# Stepper_Controller.net
KiCad netlist of a schematic drawn in EAGLE
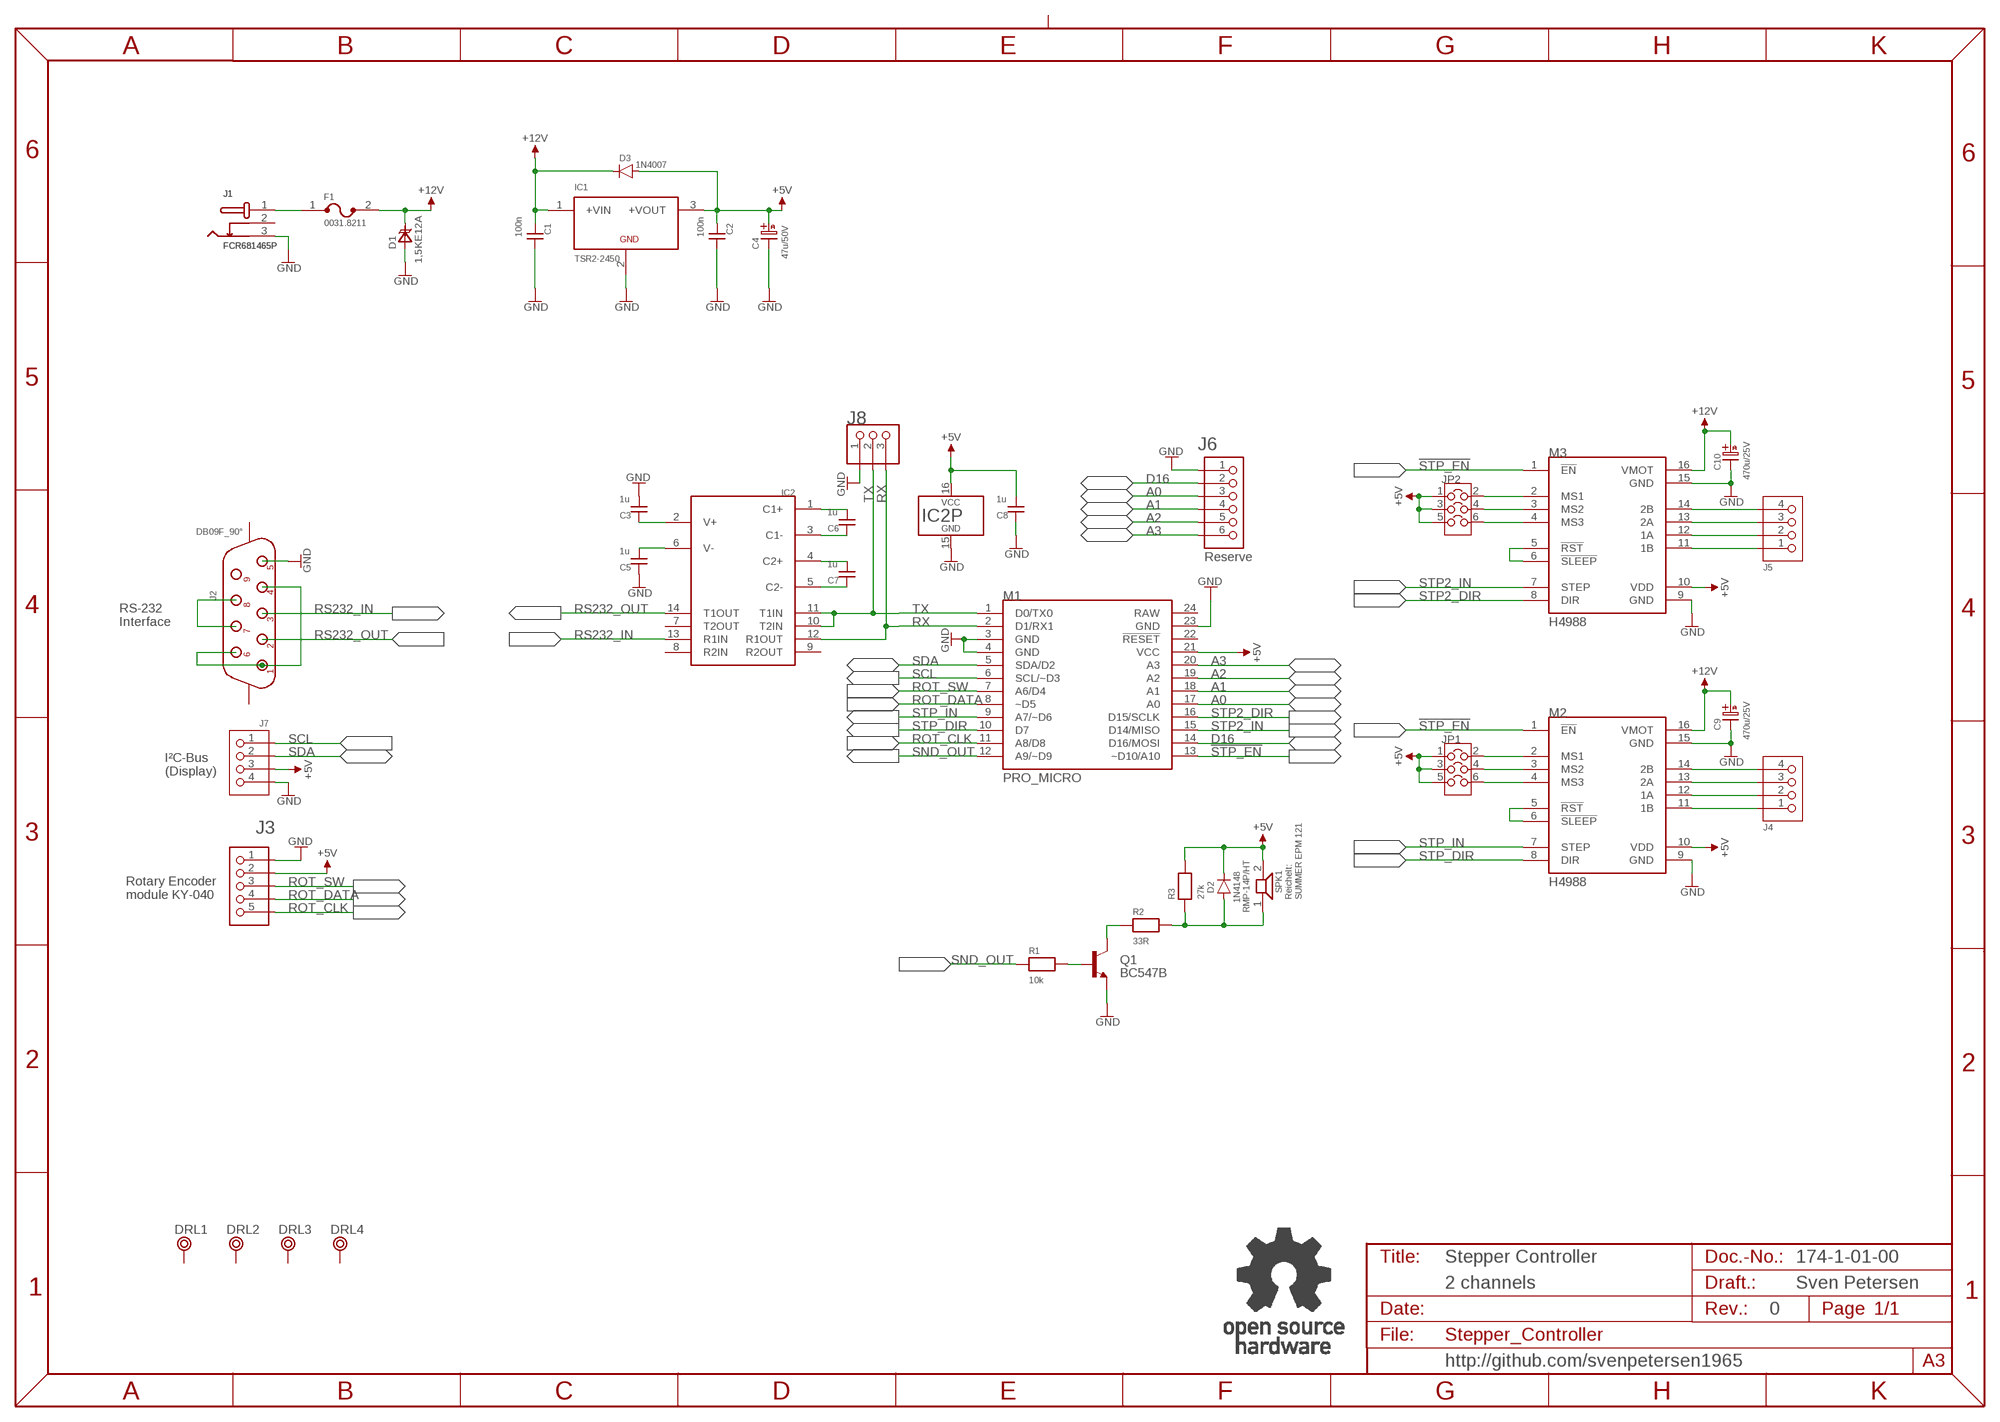
[diagram p0: schematic, sheet 1]

(export (version "E")
  (design (tool "Eeschema 10.0.6"))
  (components
    (comp (ref "C1")
      (value "100n")
      (footprint "eagle-import:C-2,5")
      (libsource (lib "eagle-import") (part "CAP01"))
    )
    (comp (ref "C2")
      (value "100n")
      (footprint "eagle-import:C-2,5")
      (libsource (lib "eagle-import") (part "CAP01"))
    )
    (comp (ref "C3")
      (value "1u")
      (footprint "eagle-import:C-5")
      (libsource (lib "eagle-import") (part "CAP02"))
    )
    (comp (ref "C4")
      (value "47u/50V")
      (footprint "eagle-import:C07_2,5")
      (libsource (lib "eagle-import") (part "C07/2,5"))
    )
    (comp (ref "C5")
      (value "1u")
      (footprint "eagle-import:C-5")
      (libsource (lib "eagle-import") (part "CAP02"))
    )
    (comp (ref "C6")
      (value "1u")
      (footprint "eagle-import:C-5")
      (libsource (lib "eagle-import") (part "CAP02"))
    )
    (comp (ref "C7")
      (value "1u")
      (footprint "eagle-import:C-5")
      (libsource (lib "eagle-import") (part "CAP02"))
    )
    (comp (ref "C8")
      (value "1u")
      (footprint "eagle-import:C-5")
      (libsource (lib "eagle-import") (part "CAP02"))
    )
    (comp (ref "C9")
      (value "470u/25V")
      (footprint "eagle-import:C08_3,5")
      (libsource (lib "eagle-import") (part "C08/3,5"))
    )
    (comp (ref "C10")
      (value "470u/25V")
      (footprint "eagle-import:C08_3,5")
      (libsource (lib "eagle-import") (part "C08/3,5"))
    )
    (comp (ref "D1")
      (value "1,5KE12A")
      (footprint "eagle-import:DO-201")
      (libsource (lib "eagle-import") (part "1,5KE12A"))
    )
    (comp (ref "D2")
      (value "1N4148")
      (footprint "eagle-import:DO-35")
      (libsource (lib "eagle-import") (part "1N4148"))
    )
    (comp (ref "D3")
      (value "1N4007")
      (footprint "eagle-import:DO-41")
      (libsource (lib "eagle-import") (part "1N4007"))
    )
    (comp (ref "DRL1")
      (value "BOHR3,5")
      (footprint "eagle-import:BOHR3,5")
      (libsource (lib "eagle-import") (part "BOHR3,5"))
    )
    (comp (ref "DRL2")
      (value "BOHR3,5")
      (footprint "eagle-import:BOHR3,5")
      (libsource (lib "eagle-import") (part "BOHR3,5"))
    )
    (comp (ref "DRL3")
      (value "BOHR3,5")
      (footprint "eagle-import:BOHR3,5")
      (libsource (lib "eagle-import") (part "BOHR3,5"))
    )
    (comp (ref "DRL4")
      (value "BOHR3,5")
      (footprint "eagle-import:BOHR3,5")
      (libsource (lib "eagle-import") (part "BOHR3,5"))
    )
    (comp (ref "F1")
      (value "0031.8211")
      (footprint "eagle-import:0031.8211")
      (libsource (lib "eagle-import") (part "0031.8211"))
    )
    (comp (ref "IC1")
      (value "TSR2-2450")
      (footprint "eagle-import:TSR2")
      (libsource (lib "eagle-import") (part "TSR2"))
    )
    (comp (ref "IC2")
      (value "MAX-232")
      (footprint "eagle-import:DIL-16")
      (libsource (lib "eagle-import") (part "MAX-232"))
    )
    (comp (ref "J1")
      (value "FCR681465P")
      (footprint "eagle-import:FCR681465P")
      (libsource (lib "eagle-import") (part "FCR681465P"))
    )
    (comp (ref "J2")
      (value "DB09F_90°")
      (footprint "eagle-import:DS09F-H")
      (libsource (lib "eagle-import") (part "DS09F-H-CL"))
    )
    (comp (ref "J3")
      (value "6410-5P")
      (footprint "eagle-import:6410-5P")
      (libsource (lib "eagle-import") (part "6410-5P"))
    )
    (comp (ref "J4")
      (value "6410-4P")
      (footprint "eagle-import:6410-4P")
      (libsource (lib "eagle-import") (part "6410-4P"))
    )
    (comp (ref "J5")
      (value "6410-4P")
      (footprint "eagle-import:6410-4P")
      (libsource (lib "eagle-import") (part "6410-4P"))
    )
    (comp (ref "J6")
      (value "PINHD-1X6")
      (footprint "eagle-import:1X06")
      (libsource (lib "eagle-import") (part "PINHD-1X6"))
    )
    (comp (ref "J7")
      (value "6410-4P")
      (footprint "eagle-import:6410-4P")
      (libsource (lib "eagle-import") (part "6410-4P"))
    )
    (comp (ref "J8")
      (value "PINHD-1X3")
      (footprint "eagle-import:1X03")
      (libsource (lib "eagle-import") (part "PINHD-1X3"))
    )
    (comp (ref "JP1")
      (value "COMBI-3X2P")
      (footprint "eagle-import:COMBI-3X2")
      (libsource (lib "eagle-import") (part "COMBI-3X2P"))
    )
    (comp (ref "JP2")
      (value "COMBI-3X2P")
      (footprint "eagle-import:COMBI-3X2")
      (libsource (lib "eagle-import") (part "COMBI-3X2P"))
    )
    (comp (ref "M1")
      (value "PRO_MICRO")
      (footprint "eagle-import:PRO_MICRO")
      (libsource (lib "eagle-import") (part "PRO_MICRO"))
    )
    (comp (ref "M2")
      (value "H4988")
      (footprint "eagle-import:H4988")
      (libsource (lib "eagle-import") (part "H4988"))
    )
    (comp (ref "M3")
      (value "H4988")
      (footprint "eagle-import:H4988")
      (libsource (lib "eagle-import") (part "H4988"))
    )
    (comp (ref "Q1")
      (value "BC547B")
      (footprint "eagle-import:TO92")
      (libsource (lib "eagle-import") (part "BC547B"))
    )
    (comp (ref "R1")
      (value "10k")
      (footprint "eagle-import:R-10")
      (libsource (lib "eagle-import") (part "RES04"))
    )
    (comp (ref "R2")
      (value "33R")
      (footprint "eagle-import:R-10")
      (libsource (lib "eagle-import") (part "RES04"))
    )
    (comp (ref "R3")
      (value "27k")
      (footprint "eagle-import:R-10")
      (libsource (lib "eagle-import") (part "RES04"))
    )
    (comp (ref "SPK1")
      (value "RMP-14P/HT")
      (footprint "eagle-import:RMP-14P_HT")
      (libsource (lib "eagle-import") (part "RMP-14P/HT"))
    )
    (comp (ref "U$2")
      (value "OPEN_SOURCE_HW")
      (footprint "eagle-import:OPENHW")
      (libsource (lib "eagle-import") (part "OPEN_SOURCE_HW"))
    )
  )
  (nets
    (net (code "1") (name "+5V") (class "Default")
      (node (ref "C2") (pin "1") (pinfunction "1_1") (pintype "passive"))
      (node (ref "C4") (pin "A") (pinfunction "+_A") (pintype "passive"))
      (node (ref "C8") (pin "2") (pinfunction "2_2") (pintype "passive"))
      (node (ref "D2") (pin "K") (pinfunction "K_K") (pintype "passive"))
      (node (ref "D3") (pin "A") (pinfunction "A_A") (pintype "passive"))
      (node (ref "IC1") (pin "3") (pinfunction "+VOUT_3") (pintype "output"))
      (node (ref "IC2") (pin "16") (pinfunction "VCC_16") (pintype "power_in"))
      (node (ref "J3") (pin "2") (pinfunction "2_2") (pintype "passive"))
      (node (ref "J7") (pin "3") (pinfunction "3_3") (pintype "passive"))
      (node (ref "JP1") (pin "1") (pinfunction "1_1") (pintype "bidirectional"))
      (node (ref "JP1") (pin "3") (pinfunction "3_3") (pintype "bidirectional"))
      (node (ref "JP1") (pin "5") (pinfunction "5_5") (pintype "bidirectional"))
      (node (ref "JP2") (pin "1") (pinfunction "1_1") (pintype "bidirectional"))
      (node (ref "JP2") (pin "3") (pinfunction "3_3") (pintype "bidirectional"))
      (node (ref "JP2") (pin "5") (pinfunction "5_5") (pintype "bidirectional"))
      (node (ref "M1") (pin "21") (pinfunction "VCC_21") (pintype "power_in"))
      (node (ref "M2") (pin "10") (pinfunction "VDD_10") (pintype "power_in"))
      (node (ref "M3") (pin "10") (pinfunction "VDD_10") (pintype "power_in"))
      (node (ref "R3") (pin "2") (pinfunction "2_2") (pintype "passive"))
      (node (ref "SPK1") (pin "2") (pinfunction "2_2") (pintype "bidirectional"))
    )
    (net (code "2") (name "+12V") (class "Default")
      (node (ref "C1") (pin "1") (pinfunction "1_1") (pintype "passive"))
      (node (ref "C10") (pin "+") (pinfunction "+_+") (pintype "passive"))
      (node (ref "C9") (pin "+") (pinfunction "+_+") (pintype "passive"))
      (node (ref "D1") (pin "K") (pinfunction "K_K") (pintype "passive"))
      (node (ref "D3") (pin "K") (pinfunction "K_K") (pintype "passive"))
      (node (ref "F1") (pin "2") (pinfunction "2_2") (pintype "passive"))
      (node (ref "IC1") (pin "1") (pinfunction "+VIN_1") (pintype "input"))
      (node (ref "M2") (pin "16") (pinfunction "VMOT_16") (pintype "power_in"))
      (node (ref "M3") (pin "16") (pinfunction "VMOT_16") (pintype "power_in"))
    )
    (net (code "3") (name "/A0") (class "Default")
      (node (ref "J6") (pin "3") (pinfunction "3_3") (pintype "passive"))
      (node (ref "M1") (pin "17") (pinfunction "A0_17") (pintype "bidirectional"))
    )
    (net (code "4") (name "/A1") (class "Default")
      (node (ref "J6") (pin "4") (pinfunction "4_4") (pintype "passive"))
      (node (ref "M1") (pin "18") (pinfunction "A1_18") (pintype "bidirectional"))
    )
    (net (code "5") (name "/A2") (class "Default")
      (node (ref "J6") (pin "5") (pinfunction "5_5") (pintype "passive"))
      (node (ref "M1") (pin "19") (pinfunction "A2_19") (pintype "bidirectional"))
    )
    (net (code "6") (name "/A3") (class "Default")
      (node (ref "J6") (pin "6") (pinfunction "6_6") (pintype "passive"))
      (node (ref "M1") (pin "20") (pinfunction "A3_20") (pintype "bidirectional"))
    )
    (net (code "7") (name "/D16") (class "Default")
      (node (ref "J6") (pin "2") (pinfunction "2_2") (pintype "passive"))
      (node (ref "M1") (pin "14") (pinfunction "D16/MOSI_14") (pintype "bidirectional"))
    )
    (net (code "8") (name "/RAW") (class "Default")
      (node (ref "M1") (pin "24") (pinfunction "RAW_24") (pintype "power_in"))
    )
    (net (code "9") (name "/ROT_CLK") (class "Default")
      (node (ref "J3") (pin "5") (pinfunction "5_5") (pintype "passive"))
      (node (ref "M1") (pin "11") (pinfunction "A8/D8_11") (pintype "bidirectional"))
    )
    (net (code "10") (name "/ROT_DATA") (class "Default")
      (node (ref "J3") (pin "4") (pinfunction "4_4") (pintype "passive"))
      (node (ref "M1") (pin "8") (pinfunction "~{D5}_8") (pintype "bidirectional"))
    )
    (net (code "11") (name "/ROT_SW") (class "Default")
      (node (ref "J3") (pin "3") (pinfunction "3_3") (pintype "passive"))
      (node (ref "M1") (pin "7") (pinfunction "A6/D4_7") (pintype "bidirectional"))
    )
    (net (code "12") (name "/RS232_IN") (class "Default")
      (node (ref "IC2") (pin "13") (pinfunction "R1IN_13") (pintype "input"))
      (node (ref "J2") (pin "3") (pinfunction "3_3") (pintype "passive"))
    )
    (net (code "13") (name "/RS232_OUT") (class "Default")
      (node (ref "IC2") (pin "14") (pinfunction "T1OUT_14") (pintype "output"))
      (node (ref "J2") (pin "2") (pinfunction "2_2") (pintype "passive"))
    )
    (net (code "14") (name "/RX") (class "Default")
      (node (ref "IC2") (pin "12") (pinfunction "R1OUT_12") (pintype "output"))
      (node (ref "J8") (pin "3") (pinfunction "3_3") (pintype "passive"))
      (node (ref "M1") (pin "2") (pinfunction "D1/RX1_2") (pintype "bidirectional"))
    )
    (net (code "15") (name "/SCL") (class "Default")
      (node (ref "J7") (pin "1") (pinfunction "1_1") (pintype "passive"))
      (node (ref "M1") (pin "6") (pinfunction "SCL/~{D3}_6") (pintype "bidirectional"))
    )
    (net (code "16") (name "/SDA") (class "Default")
      (node (ref "J7") (pin "2") (pinfunction "2_2") (pintype "passive"))
      (node (ref "M1") (pin "5") (pinfunction "SDA/D2_5") (pintype "bidirectional"))
    )
    (net (code "17") (name "/SND_OUT") (class "Default")
      (node (ref "M1") (pin "12") (pinfunction "A9/~{D9}_12") (pintype "bidirectional"))
      (node (ref "R1") (pin "1") (pinfunction "1_1") (pintype "passive"))
    )
    (net (code "18") (name "/STP2_DIR") (class "Default")
      (node (ref "M1") (pin "16") (pinfunction "D15/SCLK_16") (pintype "bidirectional"))
      (node (ref "M3") (pin "8") (pinfunction "DIR_8") (pintype "input"))
    )
    (net (code "19") (name "/STP2_IN") (class "Default")
      (node (ref "M1") (pin "15") (pinfunction "D14/MISO_15") (pintype "bidirectional"))
      (node (ref "M3") (pin "7") (pinfunction "STEP_7") (pintype "input"))
    )
    (net (code "20") (name "/STP_DIR") (class "Default")
      (node (ref "M1") (pin "10") (pinfunction "D7_10") (pintype "bidirectional"))
      (node (ref "M2") (pin "8") (pinfunction "DIR_8") (pintype "input"))
    )
    (net (code "21") (name "/STP_IN") (class "Default")
      (node (ref "M1") (pin "9") (pinfunction "A7/~{D6}_9") (pintype "bidirectional"))
      (node (ref "M2") (pin "7") (pinfunction "STEP_7") (pintype "input"))
    )
    (net (code "22") (name "/TX") (class "Default")
      (node (ref "IC2") (pin "10") (pinfunction "T2IN_10") (pintype "input"))
      (node (ref "IC2") (pin "11") (pinfunction "T1IN_11") (pintype "input"))
      (node (ref "J8") (pin "2") (pinfunction "2_2") (pintype "passive"))
      (node (ref "M1") (pin "1") (pinfunction "D0/TX0_1") (pintype "bidirectional"))
    )
    (net (code "23") (name "/~{STP_EN}") (class "Default")
      (node (ref "M1") (pin "13") (pinfunction "~{D10/A10}_13") (pintype "bidirectional"))
      (node (ref "M2") (pin "1") (pinfunction "~{EN}_1") (pintype "input"))
      (node (ref "M3") (pin "1") (pinfunction "~{EN}_1") (pintype "input"))
    )
    (net (code "24") (name "GND") (class "Default")
      (node (ref "C1") (pin "2") (pinfunction "2_2") (pintype "passive"))
      (node (ref "C10") (pin "-") (pinfunction "-_-") (pintype "passive"))
      (node (ref "C2") (pin "2") (pinfunction "2_2") (pintype "passive"))
      (node (ref "C3") (pin "2") (pinfunction "2_2") (pintype "passive"))
      (node (ref "C4") (pin "K") (pinfunction "-_K") (pintype "passive"))
      (node (ref "C5") (pin "1") (pinfunction "1_1") (pintype "passive"))
      (node (ref "C8") (pin "1") (pinfunction "1_1") (pintype "passive"))
      (node (ref "C9") (pin "-") (pinfunction "-_-") (pintype "passive"))
      (node (ref "D1") (pin "A") (pinfunction "A_A") (pintype "passive"))
      (node (ref "IC1") (pin "2") (pinfunction "GND_2") (pintype "passive"))
      (node (ref "IC2") (pin "15") (pinfunction "GND_15") (pintype "power_in"))
      (node (ref "J1") (pin "3") (pinfunction "3_3") (pintype "bidirectional"))
      (node (ref "J2") (pin "5") (pinfunction "5_5") (pintype "passive"))
      (node (ref "J3") (pin "1") (pinfunction "1_1") (pintype "passive"))
      (node (ref "J6") (pin "1") (pinfunction "1_1") (pintype "passive"))
      (node (ref "J7") (pin "4") (pinfunction "4_4") (pintype "passive"))
      (node (ref "J8") (pin "1") (pinfunction "1_1") (pintype "passive"))
      (node (ref "M1") (pin "23") (pinfunction "GND_23") (pintype "power_in"))
      (node (ref "M1") (pin "3") (pinfunction "GND_3") (pintype "power_in"))
      (node (ref "M1") (pin "4") (pinfunction "GND_4") (pintype "power_in"))
      (node (ref "M2") (pin "15") (pinfunction "GND_15") (pintype "power_in"))
      (node (ref "M2") (pin "9") (pinfunction "GND_9") (pintype "power_in"))
      (node (ref "M3") (pin "15") (pinfunction "GND_15") (pintype "power_in"))
      (node (ref "M3") (pin "9") (pinfunction "GND_9") (pintype "power_in"))
      (node (ref "Q1") (pin "1") (pinfunction "E_1") (pintype "passive"))
    )
    (net (code "25") (name "Net-(D2-PadA)") (class "Default")
      (node (ref "D2") (pin "A") (pinfunction "A_A") (pintype "passive"))
      (node (ref "R2") (pin "2") (pinfunction "2_2") (pintype "passive"))
      (node (ref "R3") (pin "1") (pinfunction "1_1") (pintype "passive"))
      (node (ref "SPK1") (pin "1") (pinfunction "1_1") (pintype "bidirectional"))
    )
    (net (code "26") (name "Net-(F1-Pad1)") (class "Default")
      (node (ref "F1") (pin "1") (pinfunction "1_1") (pintype "passive"))
      (node (ref "J1") (pin "1") (pinfunction "1_1") (pintype "bidirectional"))
    )
    (net (code "27") (name "Net-(IC2A-C1+)") (class "Default")
      (node (ref "C6") (pin "2") (pinfunction "2_2") (pintype "passive"))
      (node (ref "IC2") (pin "1") (pinfunction "C1+_1") (pintype "bidirectional"))
    )
    (net (code "28") (name "Net-(IC2A-C1-)") (class "Default")
      (node (ref "C6") (pin "1") (pinfunction "1_1") (pintype "passive"))
      (node (ref "IC2") (pin "3") (pinfunction "C1-_3") (pintype "bidirectional"))
    )
    (net (code "29") (name "Net-(IC2A-C2+)") (class "Default")
      (node (ref "C7") (pin "2") (pinfunction "2_2") (pintype "passive"))
      (node (ref "IC2") (pin "4") (pinfunction "C2+_4") (pintype "bidirectional"))
    )
    (net (code "30") (name "Net-(IC2A-C2-)") (class "Default")
      (node (ref "C7") (pin "1") (pinfunction "1_1") (pintype "passive"))
      (node (ref "IC2") (pin "5") (pinfunction "C2-_5") (pintype "bidirectional"))
    )
    (net (code "31") (name "Net-(IC2A-V+)") (class "Default")
      (node (ref "C3") (pin "1") (pinfunction "1_1") (pintype "passive"))
      (node (ref "IC2") (pin "2") (pinfunction "V+_2") (pintype "bidirectional"))
    )
    (net (code "32") (name "Net-(IC2A-V-)") (class "Default")
      (node (ref "C5") (pin "2") (pinfunction "2_2") (pintype "passive"))
      (node (ref "IC2") (pin "6") (pinfunction "V-_6") (pintype "bidirectional"))
    )
    (net (code "33") (name "Net-(J2-Pad1)") (class "Default")
      (node (ref "J2") (pin "1") (pinfunction "1_1") (pintype "passive"))
      (node (ref "J2") (pin "4") (pinfunction "4_4") (pintype "passive"))
      (node (ref "J2") (pin "6") (pinfunction "6_6") (pintype "passive"))
    )
    (net (code "34") (name "Net-(J2-Pad7)") (class "Default")
      (node (ref "J2") (pin "7") (pinfunction "7_7") (pintype "passive"))
      (node (ref "J2") (pin "8") (pinfunction "8_8") (pintype "passive"))
    )
    (net (code "35") (name "Net-(M2-1A)") (class "Default")
      (node (ref "J4") (pin "2") (pinfunction "2_2") (pintype "passive"))
      (node (ref "M2") (pin "12") (pinfunction "1A_12") (pintype "output"))
    )
    (net (code "36") (name "Net-(M2-1B)") (class "Default")
      (node (ref "J4") (pin "1") (pinfunction "1_1") (pintype "passive"))
      (node (ref "M2") (pin "11") (pinfunction "1B_11") (pintype "output"))
    )
    (net (code "37") (name "Net-(M2-2A)") (class "Default")
      (node (ref "J4") (pin "3") (pinfunction "3_3") (pintype "passive"))
      (node (ref "M2") (pin "13") (pinfunction "2A_13") (pintype "output"))
    )
    (net (code "38") (name "Net-(M2-2B)") (class "Default")
      (node (ref "J4") (pin "4") (pinfunction "4_4") (pintype "passive"))
      (node (ref "M2") (pin "14") (pinfunction "2B_14") (pintype "output"))
    )
    (net (code "39") (name "Net-(M2-MS1)") (class "Default")
      (node (ref "JP1") (pin "2") (pinfunction "2_2") (pintype "bidirectional"))
      (node (ref "M2") (pin "2") (pinfunction "MS1_2") (pintype "input"))
    )
    (net (code "40") (name "Net-(M2-MS2)") (class "Default")
      (node (ref "JP1") (pin "4") (pinfunction "4_4") (pintype "bidirectional"))
      (node (ref "M2") (pin "3") (pinfunction "MS2_3") (pintype "input"))
    )
    (net (code "41") (name "Net-(M2-MS3)") (class "Default")
      (node (ref "JP1") (pin "6") (pinfunction "6_6") (pintype "bidirectional"))
      (node (ref "M2") (pin "4") (pinfunction "MS3_4") (pintype "input"))
    )
    (net (code "42") (name "Net-(M2-~{RST})") (class "Default")
      (node (ref "M2") (pin "5") (pinfunction "~{RST}_5") (pintype "input"))
      (node (ref "M2") (pin "6") (pinfunction "~{SLEEP}_6") (pintype "input"))
    )
    (net (code "43") (name "Net-(M3-1A)") (class "Default")
      (node (ref "J5") (pin "2") (pinfunction "2_2") (pintype "passive"))
      (node (ref "M3") (pin "12") (pinfunction "1A_12") (pintype "output"))
    )
    (net (code "44") (name "Net-(M3-1B)") (class "Default")
      (node (ref "J5") (pin "1") (pinfunction "1_1") (pintype "passive"))
      (node (ref "M3") (pin "11") (pinfunction "1B_11") (pintype "output"))
    )
    (net (code "45") (name "Net-(M3-2A)") (class "Default")
      (node (ref "J5") (pin "3") (pinfunction "3_3") (pintype "passive"))
      (node (ref "M3") (pin "13") (pinfunction "2A_13") (pintype "output"))
    )
    (net (code "46") (name "Net-(M3-2B)") (class "Default")
      (node (ref "J5") (pin "4") (pinfunction "4_4") (pintype "passive"))
      (node (ref "M3") (pin "14") (pinfunction "2B_14") (pintype "output"))
    )
    (net (code "47") (name "Net-(M3-MS1)") (class "Default")
      (node (ref "JP2") (pin "2") (pinfunction "2_2") (pintype "bidirectional"))
      (node (ref "M3") (pin "2") (pinfunction "MS1_2") (pintype "input"))
    )
    (net (code "48") (name "Net-(M3-MS2)") (class "Default")
      (node (ref "JP2") (pin "4") (pinfunction "4_4") (pintype "bidirectional"))
      (node (ref "M3") (pin "3") (pinfunction "MS2_3") (pintype "input"))
    )
    (net (code "49") (name "Net-(M3-MS3)") (class "Default")
      (node (ref "JP2") (pin "6") (pinfunction "6_6") (pintype "bidirectional"))
      (node (ref "M3") (pin "4") (pinfunction "MS3_4") (pintype "input"))
    )
    (net (code "50") (name "Net-(M3-~{RST})") (class "Default")
      (node (ref "M3") (pin "5") (pinfunction "~{RST}_5") (pintype "input"))
      (node (ref "M3") (pin "6") (pinfunction "~{SLEEP}_6") (pintype "input"))
    )
    (net (code "51") (name "Net-(Q1-B)") (class "Default")
      (node (ref "Q1") (pin "2") (pinfunction "B_2") (pintype "passive"))
      (node (ref "R1") (pin "2") (pinfunction "2_2") (pintype "passive"))
    )
    (net (code "52") (name "Net-(Q1-C)") (class "Default")
      (node (ref "Q1") (pin "3") (pinfunction "C_3") (pintype "passive"))
      (node (ref "R2") (pin "1") (pinfunction "1_1") (pintype "passive"))
    )
    (net (code "53") (name "unconnected-(DRL1-PadP$1)") (class "Default")
      (node (ref "DRL1") (pin "P$1") (pinfunction "P$1_P$1") (pintype "passive"))
    )
    (net (code "54") (name "unconnected-(DRL2-PadP$1)") (class "Default")
      (node (ref "DRL2") (pin "P$1") (pinfunction "P$1_P$1") (pintype "passive"))
    )
    (net (code "55") (name "unconnected-(DRL3-PadP$1)") (class "Default")
      (node (ref "DRL3") (pin "P$1") (pinfunction "P$1_P$1") (pintype "passive"))
    )
    (net (code "56") (name "unconnected-(DRL4-PadP$1)") (class "Default")
      (node (ref "DRL4") (pin "P$1") (pinfunction "P$1_P$1") (pintype "passive"))
    )
    (net (code "57") (name "unconnected-(IC2A-R2IN-Pad8)") (class "Default")
      (node (ref "IC2") (pin "8") (pinfunction "R2IN_8") (pintype "input"))
    )
    (net (code "58") (name "unconnected-(IC2A-R2OUT-Pad9)") (class "Default")
      (node (ref "IC2") (pin "9") (pinfunction "R2OUT_9") (pintype "output"))
    )
    (net (code "59") (name "unconnected-(IC2A-T2OUT-Pad7)") (class "Default")
      (node (ref "IC2") (pin "7") (pinfunction "T2OUT_7") (pintype "output"))
    )
    (net (code "60") (name "unconnected-(J1-Pad2)") (class "Default")
      (node (ref "J1") (pin "2") (pinfunction "2_2") (pintype "bidirectional"))
    )
    (net (code "61") (name "unconnected-(J2-Pad9)") (class "Default")
      (node (ref "J2") (pin "9") (pinfunction "9_9") (pintype "passive"))
    )
    (net (code "62") (name "unconnected-(J2-PadPE1)") (class "Default")
      (node (ref "J2") (pin "PE1") (pinfunction "PE1_PE1") (pintype "passive"))
    )
    (net (code "63") (name "unconnected-(J2-PadPE2)") (class "Default")
      (node (ref "J2") (pin "PE2") (pinfunction "PE2_PE2") (pintype "passive"))
    )
    (net (code "64") (name "unconnected-(M1-~{RESET}-Pad22)") (class "Default")
      (node (ref "M1") (pin "22") (pinfunction "~{RESET}_22") (pintype "bidirectional"))
    )
  )
)
